# PCB-SLIDER20.net
KiCad netlist of a schematic drawn in EAGLE
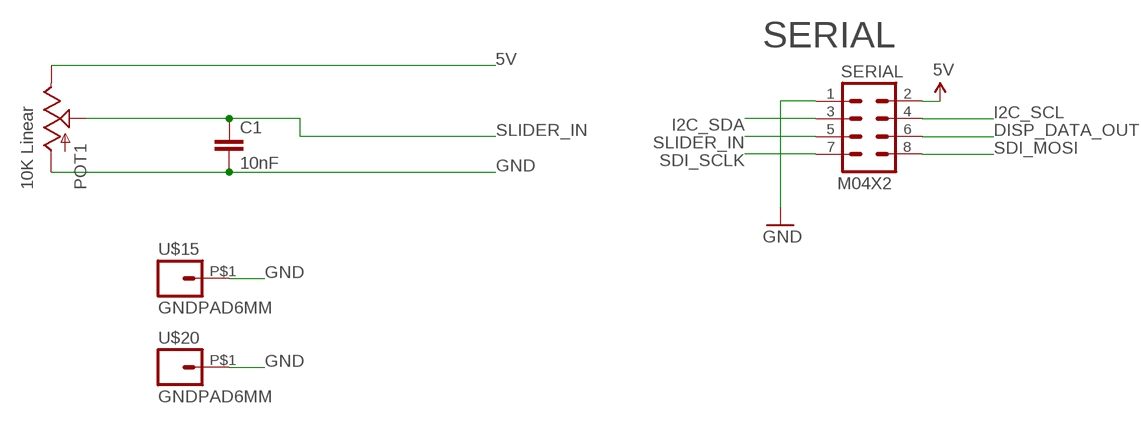
[diagram p0: schematic, sheet 1]

(export (version "E")
  (design (tool "Eeschema 10.0.6"))
  (components
    (comp (ref "C1")
      (value "10nF")
      (footprint "eagle-import:0603-CAP")
      (libsource (lib "eagle-import") (part "CAP0603-CAP"))
    )
    (comp (ref "POT1")
      (value "10K Linear")
      (footprint "eagle-import:SLIDER20")
      (libsource (lib "eagle-import") (part "SLIDER20"))
    )
    (comp (ref "SERIAL")
      (value "M04X2")
      (footprint "eagle-import:2X4")
      (libsource (lib "eagle-import") (part "M04X2"))
    )
    (comp (ref "U$15")
      (value "GNDPAD6MM")
      (footprint "eagle-import:3.2MMPAD6MM")
      (libsource (lib "eagle-import") (part "GNDPAD6MM"))
    )
    (comp (ref "U$20")
      (value "GNDPAD6MM")
      (footprint "eagle-import:3.2MMPAD6MM")
      (libsource (lib "eagle-import") (part "GNDPAD6MM"))
    )
  )
  (nets
    (net (code "1") (name "/DISP_DATA_OUT") (class "Default")
      (node (ref "SERIAL") (pin "6") (pinfunction "6_6") (pintype "passive"))
    )
    (net (code "2") (name "/I2C_SCL") (class "Default")
      (node (ref "SERIAL") (pin "4") (pinfunction "4_4") (pintype "passive"))
    )
    (net (code "3") (name "/I2C_SDA") (class "Default")
      (node (ref "SERIAL") (pin "3") (pinfunction "3_3") (pintype "passive"))
    )
    (net (code "4") (name "/SDI_MOSI") (class "Default")
      (node (ref "SERIAL") (pin "8") (pinfunction "8_8") (pintype "passive"))
    )
    (net (code "5") (name "/SDI_SCLK") (class "Default")
      (node (ref "SERIAL") (pin "7") (pinfunction "7_7") (pintype "passive"))
    )
    (net (code "6") (name "/SLIDER_IN") (class "Default")
      (node (ref "C1") (pin "1") (pinfunction "1_1") (pintype "passive"))
      (node (ref "POT1") (pin "2A") (pinfunction "S_2A") (pintype "passive"))
      (node (ref "SERIAL") (pin "5") (pinfunction "5_5") (pintype "passive"))
    )
    (net (code "7") (name "5V") (class "Default")
      (node (ref "POT1") (pin "1") (pinfunction "E_1") (pintype "passive"))
      (node (ref "SERIAL") (pin "2") (pinfunction "2_2") (pintype "passive"))
    )
    (net (code "8") (name "GND") (class "Default")
      (node (ref "C1") (pin "2") (pinfunction "2_2") (pintype "passive"))
      (node (ref "POT1") (pin "3") (pinfunction "A_3") (pintype "passive"))
      (node (ref "SERIAL") (pin "1") (pinfunction "1_1") (pintype "passive"))
      (node (ref "U$15") (pin "P$1") (pinfunction "1_P$1") (pintype "passive"))
      (node (ref "U$20") (pin "P$1") (pinfunction "1_P$1") (pintype "passive"))
    )
  )
)
